# Rx.net
KiCad netlist of a schematic drawn in EAGLE
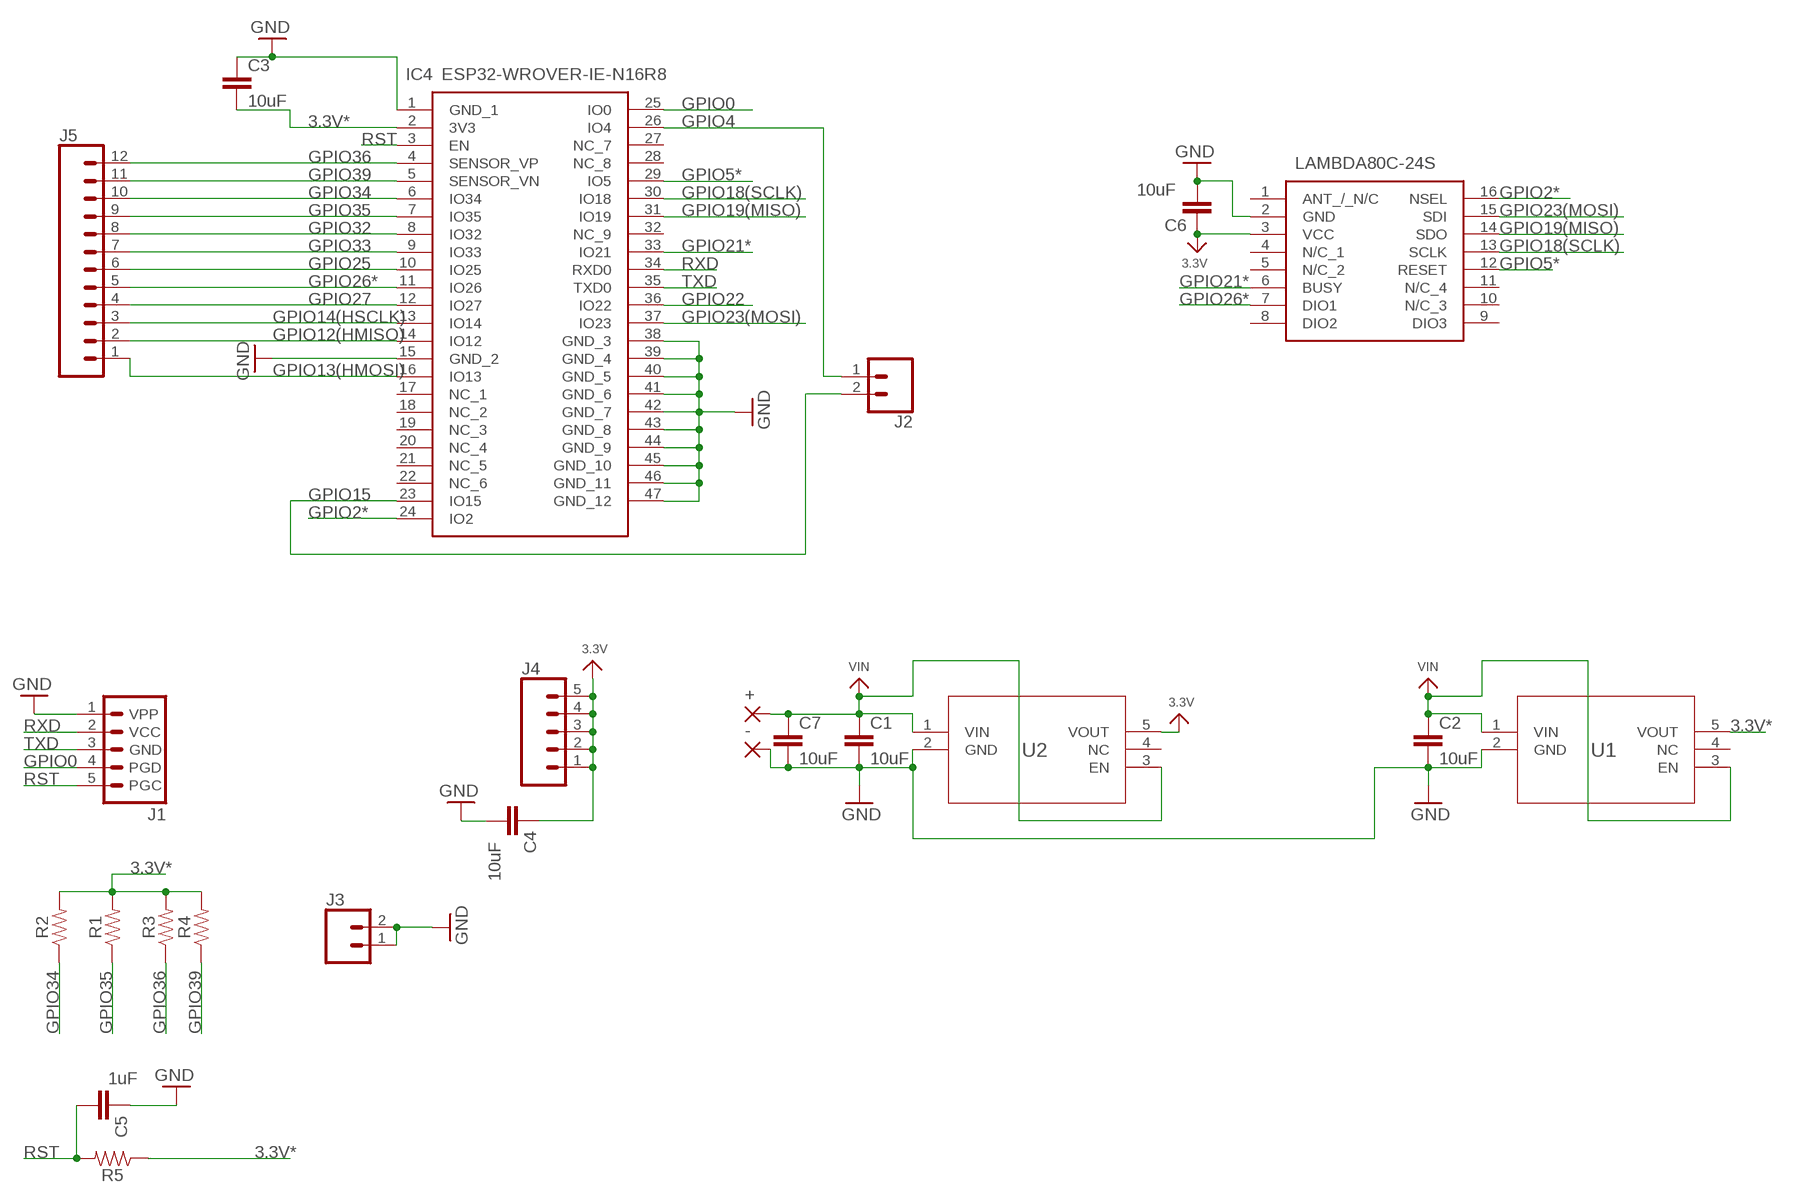
[diagram p0: schematic, sheet 1]

(export (version "E")
  (design (tool "Eeschema 10.0.6"))
  (components
    (comp (ref "+")
      (value "2,15/1,0")
      (footprint "eagle-import:2,15_1,0")
      (libsource (lib "eagle-import") (part "2,15/1,0"))
    )
    (comp (ref "-")
      (value "2,15/1,0")
      (footprint "eagle-import:2,15_1,0")
      (libsource (lib "eagle-import") (part "2,15/1,0"))
    )
    (comp (ref "C1")
      (value "10uF")
      (footprint "eagle-import:0805")
      (libsource (lib "eagle-import") (part "10UF-0805-10V-10%"))
    )
    (comp (ref "C2")
      (value "10uF")
      (footprint "eagle-import:0805")
      (libsource (lib "eagle-import") (part "10UF-0805-10V-10%"))
    )
    (comp (ref "C3")
      (value "10uF")
      (footprint "eagle-import:0805")
      (libsource (lib "eagle-import") (part "10UF-0805-10V-10%"))
    )
    (comp (ref "C4")
      (value "10uF")
      (footprint "eagle-import:0805")
      (libsource (lib "eagle-import") (part "10UF-0805-10V-10%"))
    )
    (comp (ref "C5")
      (value "1uF")
      (footprint "eagle-import:0805")
      (libsource (lib "eagle-import") (part "10UF-0805-10V-10%"))
    )
    (comp (ref "C6")
      (value "10uF")
      (footprint "eagle-import:0805")
      (libsource (lib "eagle-import") (part "10UF-0805-10V-10%"))
    )
    (comp (ref "C7")
      (value "10uF")
      (footprint "eagle-import:0805")
      (libsource (lib "eagle-import") (part "10UF-0805-10V-10%"))
    )
    (comp (ref "IC1")
      (value "LAMBDA80C-24S")
      (footprint "eagle-import:LAMBDA80C24S")
      (fields (field (name "MOUSER_PART_NUMBER") "223-LAMBDA80C-24S"))
      (libsource (lib "eagle-import") (part "LAMBDA80C-24S"))
    )
    (comp (ref "IC4")
      (value "ESP32-WROVER-IE-N16R8")
      (footprint "eagle-import:ESP32WROVERIEN16R8")
      (fields
        (field (name "MANUFACTURER_PART_NUMBER") "ESP32-Wrover-IE-N16R8")
        (field (name "MOUSER_PART_NUMBER") "356-ESP32WRVIE2864UC")
      )
      (libsource (lib "eagle-import") (part "ESP32-WROVER-IE-N16R8"))
    )
    (comp (ref "J1")
      (value "PIC_ICSP_MINI_5_PIN")
      (footprint "eagle-import:PIC_ICSP_MINI_5_PIN")
      (libsource (lib "eagle-import") (part "PIC_ICSP_MINI_5_PIN"))
    )
    (comp (ref "J2")
      (value "CONN_021X02_NO_SILK")
      (footprint "eagle-import:1X02_NO_SILK")
      (libsource (lib "eagle-import") (part "CONN_021X02_NO_SILK"))
    )
    (comp (ref "J3")
      (value "CONN_021X02_NO_SILK")
      (footprint "eagle-import:1X02_NO_SILK")
      (libsource (lib "eagle-import") (part "CONN_021X02_NO_SILK"))
    )
    (comp (ref "J4")
      (value "CONN_05NO_SILK")
      (footprint "eagle-import:1X05_NO_SILK")
      (libsource (lib "eagle-import") (part "CONN_05NO_SILK"))
    )
    (comp (ref "J5")
      (value "CONN_12NO_SILK")
      (footprint "eagle-import:1X12_NO_SILK")
      (libsource (lib "eagle-import") (part "CONN_12NO_SILK"))
    )
    (comp (ref "R1")
      (value "0")
      (footprint "eagle-import:0603")
      (libsource (lib "eagle-import") (part "0OHM-0603-1/10W-5%"))
    )
    (comp (ref "R2")
      (value "0")
      (footprint "eagle-import:0603")
      (libsource (lib "eagle-import") (part "0OHM-0603-1/10W-5%"))
    )
    (comp (ref "R3")
      (value "0")
      (footprint "eagle-import:0603")
      (libsource (lib "eagle-import") (part "0OHM-0603-1/10W-5%"))
    )
    (comp (ref "R4")
      (value "0")
      (footprint "eagle-import:0603")
      (libsource (lib "eagle-import") (part "0OHM-0603-1/10W-5%"))
    )
    (comp (ref "R5")
      (value "0")
      (footprint "eagle-import:0603")
      (libsource (lib "eagle-import") (part "0OHM-0603-1/10W-5%"))
    )
    (comp (ref "U1")
      (value "AP2112K-3.3TRG1SOT_RG1_DIO-L")
      (footprint "eagle-import:SOT_RG1_DIO-L")
      (fields
        (field (name "MANUFACTURER_PART_NUMBER") "AP2112K-3.3TRG1")
        (field (name "COPYRIGHT") "Copyright (C) 2023 Ultra Librarian. All rights reserved.")
      )
      (libsource (lib "eagle-import") (part "AP2112K-3.3TRG1SOT_RG1_DIO-L"))
    )
    (comp (ref "U2")
      (value "AP2112K-3.3TRG1SOT_RG1_DIO-L")
      (footprint "eagle-import:SOT_RG1_DIO-L")
      (fields
        (field (name "MANUFACTURER_PART_NUMBER") "AP2112K-3.3TRG1")
        (field (name "COPYRIGHT") "Copyright (C) 2023 Ultra Librarian. All rights reserved.")
      )
      (libsource (lib "eagle-import") (part "AP2112K-3.3TRG1SOT_RG1_DIO-L"))
    )
  )
  (nets
    (net (code "1") (name "/3.3V*") (class "Default")
      (node (ref "C3") (pin "2") (pinfunction "2_2") (pintype "passive"))
      (node (ref "IC4") (pin "2") (pinfunction "3V3_2") (pintype "bidirectional"))
      (node (ref "R1") (pin "2") (pinfunction "2_2") (pintype "passive"))
      (node (ref "R2") (pin "2") (pinfunction "2_2") (pintype "passive"))
      (node (ref "R3") (pin "2") (pinfunction "2_2") (pintype "passive"))
      (node (ref "R4") (pin "2") (pinfunction "2_2") (pintype "passive"))
      (node (ref "R5") (pin "1") (pinfunction "1_1") (pintype "passive"))
      (node (ref "U1") (pin "5") (pinfunction "VOUT_5") (pintype "passive"))
    )
    (net (code "2") (name "/GPIO0") (class "Default")
      (node (ref "IC4") (pin "25") (pinfunction "IO0_25") (pintype "bidirectional"))
      (node (ref "J1") (pin "4") (pinfunction "PGD_4") (pintype "passive"))
    )
    (net (code "3") (name "/GPIO2*") (class "Default")
      (node (ref "IC1") (pin "16") (pinfunction "NSEL_16") (pintype "bidirectional"))
      (node (ref "IC4") (pin "24") (pinfunction "IO2_24") (pintype "bidirectional"))
    )
    (net (code "4") (name "/GPIO4") (class "Default")
      (node (ref "IC4") (pin "26") (pinfunction "IO4_26") (pintype "bidirectional"))
      (node (ref "J2") (pin "1") (pinfunction "1_1") (pintype "passive"))
    )
    (net (code "5") (name "/GPIO5*") (class "Default")
      (node (ref "IC1") (pin "12") (pinfunction "RESET_12") (pintype "bidirectional"))
      (node (ref "IC4") (pin "29") (pinfunction "IO5_29") (pintype "bidirectional"))
    )
    (net (code "6") (name "/GPIO12(HMISO)") (class "Default")
      (node (ref "IC4") (pin "14") (pinfunction "IO12_14") (pintype "bidirectional"))
      (node (ref "J5") (pin "2") (pinfunction "2_2") (pintype "passive"))
    )
    (net (code "7") (name "/GPIO13(HMOSI)") (class "Default")
      (node (ref "IC4") (pin "16") (pinfunction "IO13_16") (pintype "bidirectional"))
      (node (ref "J5") (pin "1") (pinfunction "1_1") (pintype "passive"))
    )
    (net (code "8") (name "/GPIO14(HSCLK)") (class "Default")
      (node (ref "IC4") (pin "13") (pinfunction "IO14_13") (pintype "bidirectional"))
      (node (ref "J5") (pin "3") (pinfunction "3_3") (pintype "passive"))
    )
    (net (code "9") (name "/GPIO15") (class "Default")
      (node (ref "IC4") (pin "23") (pinfunction "IO15_23") (pintype "bidirectional"))
      (node (ref "J2") (pin "2") (pinfunction "2_2") (pintype "passive"))
    )
    (net (code "10") (name "/GPIO18(SCLK)") (class "Default")
      (node (ref "IC1") (pin "13") (pinfunction "SCLK_13") (pintype "bidirectional"))
      (node (ref "IC4") (pin "30") (pinfunction "IO18_30") (pintype "bidirectional"))
    )
    (net (code "11") (name "/GPIO19(MISO)") (class "Default")
      (node (ref "IC1") (pin "14") (pinfunction "SDO_14") (pintype "bidirectional"))
      (node (ref "IC4") (pin "31") (pinfunction "IO19_31") (pintype "bidirectional"))
    )
    (net (code "12") (name "/GPIO21*") (class "Default")
      (node (ref "IC1") (pin "6") (pinfunction "BUSY_6") (pintype "bidirectional"))
      (node (ref "IC4") (pin "33") (pinfunction "IO21_33") (pintype "bidirectional"))
    )
    (net (code "13") (name "/GPIO22") (class "Default")
      (node (ref "IC4") (pin "36") (pinfunction "IO22_36") (pintype "bidirectional"))
    )
    (net (code "14") (name "/GPIO23(MOSI)") (class "Default")
      (node (ref "IC1") (pin "15") (pinfunction "SDI_15") (pintype "bidirectional"))
      (node (ref "IC4") (pin "37") (pinfunction "IO23_37") (pintype "bidirectional"))
    )
    (net (code "15") (name "/GPIO25") (class "Default")
      (node (ref "IC4") (pin "10") (pinfunction "IO25_10") (pintype "bidirectional"))
      (node (ref "J5") (pin "6") (pinfunction "6_6") (pintype "passive"))
    )
    (net (code "16") (name "/GPIO26*") (class "Default")
      (node (ref "IC1") (pin "7") (pinfunction "DIO1_7") (pintype "bidirectional"))
      (node (ref "IC4") (pin "11") (pinfunction "IO26_11") (pintype "bidirectional"))
      (node (ref "J5") (pin "5") (pinfunction "5_5") (pintype "passive"))
    )
    (net (code "17") (name "/GPIO27") (class "Default")
      (node (ref "IC4") (pin "12") (pinfunction "IO27_12") (pintype "bidirectional"))
      (node (ref "J5") (pin "4") (pinfunction "4_4") (pintype "passive"))
    )
    (net (code "18") (name "/GPIO32") (class "Default")
      (node (ref "IC4") (pin "8") (pinfunction "IO32_8") (pintype "bidirectional"))
      (node (ref "J5") (pin "8") (pinfunction "8_8") (pintype "passive"))
    )
    (net (code "19") (name "/GPIO33") (class "Default")
      (node (ref "IC4") (pin "9") (pinfunction "IO33_9") (pintype "bidirectional"))
      (node (ref "J5") (pin "7") (pinfunction "7_7") (pintype "passive"))
    )
    (net (code "20") (name "/GPIO34") (class "Default")
      (node (ref "IC4") (pin "6") (pinfunction "IO34_6") (pintype "bidirectional"))
      (node (ref "J5") (pin "10") (pinfunction "10_10") (pintype "passive"))
      (node (ref "R2") (pin "1") (pinfunction "1_1") (pintype "passive"))
    )
    (net (code "21") (name "/GPIO35") (class "Default")
      (node (ref "IC4") (pin "7") (pinfunction "IO35_7") (pintype "bidirectional"))
      (node (ref "J5") (pin "9") (pinfunction "9_9") (pintype "passive"))
      (node (ref "R1") (pin "1") (pinfunction "1_1") (pintype "passive"))
    )
    (net (code "22") (name "/GPIO36") (class "Default")
      (node (ref "IC4") (pin "4") (pinfunction "SENSOR_VP_4") (pintype "bidirectional"))
      (node (ref "J5") (pin "12") (pinfunction "12_12") (pintype "passive"))
      (node (ref "R3") (pin "1") (pinfunction "1_1") (pintype "passive"))
    )
    (net (code "23") (name "/GPIO39") (class "Default")
      (node (ref "IC4") (pin "5") (pinfunction "SENSOR_VN_5") (pintype "bidirectional"))
      (node (ref "J5") (pin "11") (pinfunction "11_11") (pintype "passive"))
      (node (ref "R4") (pin "1") (pinfunction "1_1") (pintype "passive"))
    )
    (net (code "24") (name "/RST") (class "Default")
      (node (ref "C5") (pin "2") (pinfunction "2_2") (pintype "passive"))
      (node (ref "IC4") (pin "3") (pinfunction "EN_3") (pintype "bidirectional"))
      (node (ref "J1") (pin "5") (pinfunction "PGC_5") (pintype "passive"))
      (node (ref "R5") (pin "2") (pinfunction "2_2") (pintype "passive"))
    )
    (net (code "25") (name "/RXD") (class "Default")
      (node (ref "IC4") (pin "34") (pinfunction "RXD0_34") (pintype "bidirectional"))
      (node (ref "J1") (pin "2") (pinfunction "VCC_2") (pintype "passive"))
    )
    (net (code "26") (name "/TXD") (class "Default")
      (node (ref "IC4") (pin "35") (pinfunction "TXD0_35") (pintype "bidirectional"))
      (node (ref "J1") (pin "3") (pinfunction "GND_3") (pintype "passive"))
    )
    (net (code "27") (name "3.3V") (class "Default")
      (node (ref "C4") (pin "1") (pinfunction "1_1") (pintype "passive"))
      (node (ref "C6") (pin "1") (pinfunction "1_1") (pintype "passive"))
      (node (ref "IC1") (pin "3") (pinfunction "VCC_3") (pintype "bidirectional"))
      (node (ref "J4") (pin "1") (pinfunction "1_1") (pintype "passive"))
      (node (ref "J4") (pin "2") (pinfunction "2_2") (pintype "passive"))
      (node (ref "J4") (pin "3") (pinfunction "3_3") (pintype "passive"))
      (node (ref "J4") (pin "4") (pinfunction "4_4") (pintype "passive"))
      (node (ref "J4") (pin "5") (pinfunction "5_5") (pintype "passive"))
      (node (ref "U2") (pin "5") (pinfunction "VOUT_5") (pintype "passive"))
    )
    (net (code "28") (name "GND") (class "Default")
      (node (ref "-") (pin "1") (pinfunction "P_1") (pintype "passive"))
      (node (ref "C1") (pin "2") (pinfunction "2_2") (pintype "passive"))
      (node (ref "C2") (pin "2") (pinfunction "2_2") (pintype "passive"))
      (node (ref "C3") (pin "1") (pinfunction "1_1") (pintype "passive"))
      (node (ref "C4") (pin "2") (pinfunction "2_2") (pintype "passive"))
      (node (ref "C5") (pin "1") (pinfunction "1_1") (pintype "passive"))
      (node (ref "C6") (pin "2") (pinfunction "2_2") (pintype "passive"))
      (node (ref "C7") (pin "2") (pinfunction "2_2") (pintype "passive"))
      (node (ref "IC1") (pin "2") (pinfunction "GND_2") (pintype "bidirectional"))
      (node (ref "IC4") (pin "1") (pinfunction "GND_1_1") (pintype "bidirectional"))
      (node (ref "IC4") (pin "15") (pinfunction "GND_2_15") (pintype "bidirectional"))
      (node (ref "IC4") (pin "38") (pinfunction "GND_3_38") (pintype "bidirectional"))
      (node (ref "IC4") (pin "39") (pinfunction "GND_4_39") (pintype "bidirectional"))
      (node (ref "IC4") (pin "40") (pinfunction "GND_5_40") (pintype "bidirectional"))
      (node (ref "IC4") (pin "41") (pinfunction "GND_6_41") (pintype "bidirectional"))
      (node (ref "IC4") (pin "42") (pinfunction "GND_7_42") (pintype "bidirectional"))
      (node (ref "IC4") (pin "43") (pinfunction "GND_8_43") (pintype "bidirectional"))
      (node (ref "IC4") (pin "44") (pinfunction "GND_9_44") (pintype "bidirectional"))
      (node (ref "IC4") (pin "45") (pinfunction "GND_10_45") (pintype "bidirectional"))
      (node (ref "IC4") (pin "46") (pinfunction "GND_11_46") (pintype "bidirectional"))
      (node (ref "IC4") (pin "47") (pinfunction "GND_12_47") (pintype "bidirectional"))
      (node (ref "J1") (pin "1") (pinfunction "VPP_1") (pintype "passive"))
      (node (ref "J3") (pin "1") (pinfunction "1_1") (pintype "passive"))
      (node (ref "J3") (pin "2") (pinfunction "2_2") (pintype "passive"))
      (node (ref "U1") (pin "2") (pinfunction "GND_2") (pintype "passive"))
      (node (ref "U2") (pin "2") (pinfunction "GND_2") (pintype "passive"))
    )
    (net (code "29") (name "VIN") (class "Default")
      (node (ref "+") (pin "1") (pinfunction "P_1") (pintype "passive"))
      (node (ref "C1") (pin "1") (pinfunction "1_1") (pintype "passive"))
      (node (ref "C2") (pin "1") (pinfunction "1_1") (pintype "passive"))
      (node (ref "C7") (pin "1") (pinfunction "1_1") (pintype "passive"))
      (node (ref "U1") (pin "1") (pinfunction "VIN_1") (pintype "passive"))
      (node (ref "U1") (pin "3") (pinfunction "EN_3") (pintype "passive"))
      (node (ref "U2") (pin "1") (pinfunction "VIN_1") (pintype "passive"))
      (node (ref "U2") (pin "3") (pinfunction "EN_3") (pintype "passive"))
    )
    (net (code "30") (name "unconnected-(IC1-ANT_{slash}_N{slash}C-Pad1)") (class "Default")
      (node (ref "IC1") (pin "1") (pinfunction "ANT_/_N/C_1") (pintype "bidirectional"))
    )
    (net (code "31") (name "unconnected-(IC1-DIO2-Pad8)") (class "Default")
      (node (ref "IC1") (pin "8") (pinfunction "DIO2_8") (pintype "bidirectional"))
    )
    (net (code "32") (name "unconnected-(IC1-DIO3-Pad9)") (class "Default")
      (node (ref "IC1") (pin "9") (pinfunction "DIO3_9") (pintype "bidirectional"))
    )
    (net (code "33") (name "unconnected-(IC1-N{slash}C_1-Pad4)") (class "Default")
      (node (ref "IC1") (pin "4") (pinfunction "N/C_1_4") (pintype "bidirectional"))
    )
    (net (code "34") (name "unconnected-(IC1-N{slash}C_2-Pad5)") (class "Default")
      (node (ref "IC1") (pin "5") (pinfunction "N/C_2_5") (pintype "bidirectional"))
    )
    (net (code "35") (name "unconnected-(IC1-N{slash}C_3-Pad10)") (class "Default")
      (node (ref "IC1") (pin "10") (pinfunction "N/C_3_10") (pintype "bidirectional"))
    )
    (net (code "36") (name "unconnected-(IC1-N{slash}C_4-Pad11)") (class "Default")
      (node (ref "IC1") (pin "11") (pinfunction "N/C_4_11") (pintype "bidirectional"))
    )
    (net (code "37") (name "unconnected-(IC4-NC_1-Pad17)") (class "Default")
      (node (ref "IC4") (pin "17") (pinfunction "NC_1_17") (pintype "bidirectional"))
    )
    (net (code "38") (name "unconnected-(IC4-NC_2-Pad18)") (class "Default")
      (node (ref "IC4") (pin "18") (pinfunction "NC_2_18") (pintype "bidirectional"))
    )
    (net (code "39") (name "unconnected-(IC4-NC_3-Pad19)") (class "Default")
      (node (ref "IC4") (pin "19") (pinfunction "NC_3_19") (pintype "bidirectional"))
    )
    (net (code "40") (name "unconnected-(IC4-NC_4-Pad20)") (class "Default")
      (node (ref "IC4") (pin "20") (pinfunction "NC_4_20") (pintype "bidirectional"))
    )
    (net (code "41") (name "unconnected-(IC4-NC_5-Pad21)") (class "Default")
      (node (ref "IC4") (pin "21") (pinfunction "NC_5_21") (pintype "bidirectional"))
    )
    (net (code "42") (name "unconnected-(IC4-NC_6-Pad22)") (class "Default")
      (node (ref "IC4") (pin "22") (pinfunction "NC_6_22") (pintype "bidirectional"))
    )
    (net (code "43") (name "unconnected-(IC4-NC_7-Pad27)") (class "Default")
      (node (ref "IC4") (pin "27") (pinfunction "NC_7_27") (pintype "bidirectional"))
    )
    (net (code "44") (name "unconnected-(IC4-NC_8-Pad28)") (class "Default")
      (node (ref "IC4") (pin "28") (pinfunction "NC_8_28") (pintype "bidirectional"))
    )
    (net (code "45") (name "unconnected-(IC4-NC_9-Pad32)") (class "Default")
      (node (ref "IC4") (pin "32") (pinfunction "NC_9_32") (pintype "bidirectional"))
    )
    (net (code "46") (name "unconnected-(U1-NC-Pad4)") (class "Default")
      (node (ref "U1") (pin "4") (pinfunction "NC_4") (pintype "passive"))
    )
    (net (code "47") (name "unconnected-(U2-NC-Pad4)") (class "Default")
      (node (ref "U2") (pin "4") (pinfunction "NC_4") (pintype "passive"))
    )
  )
)
